# BYH_USBHUB.net
KiCad netlist of a schematic drawn in EasyEDA Pro
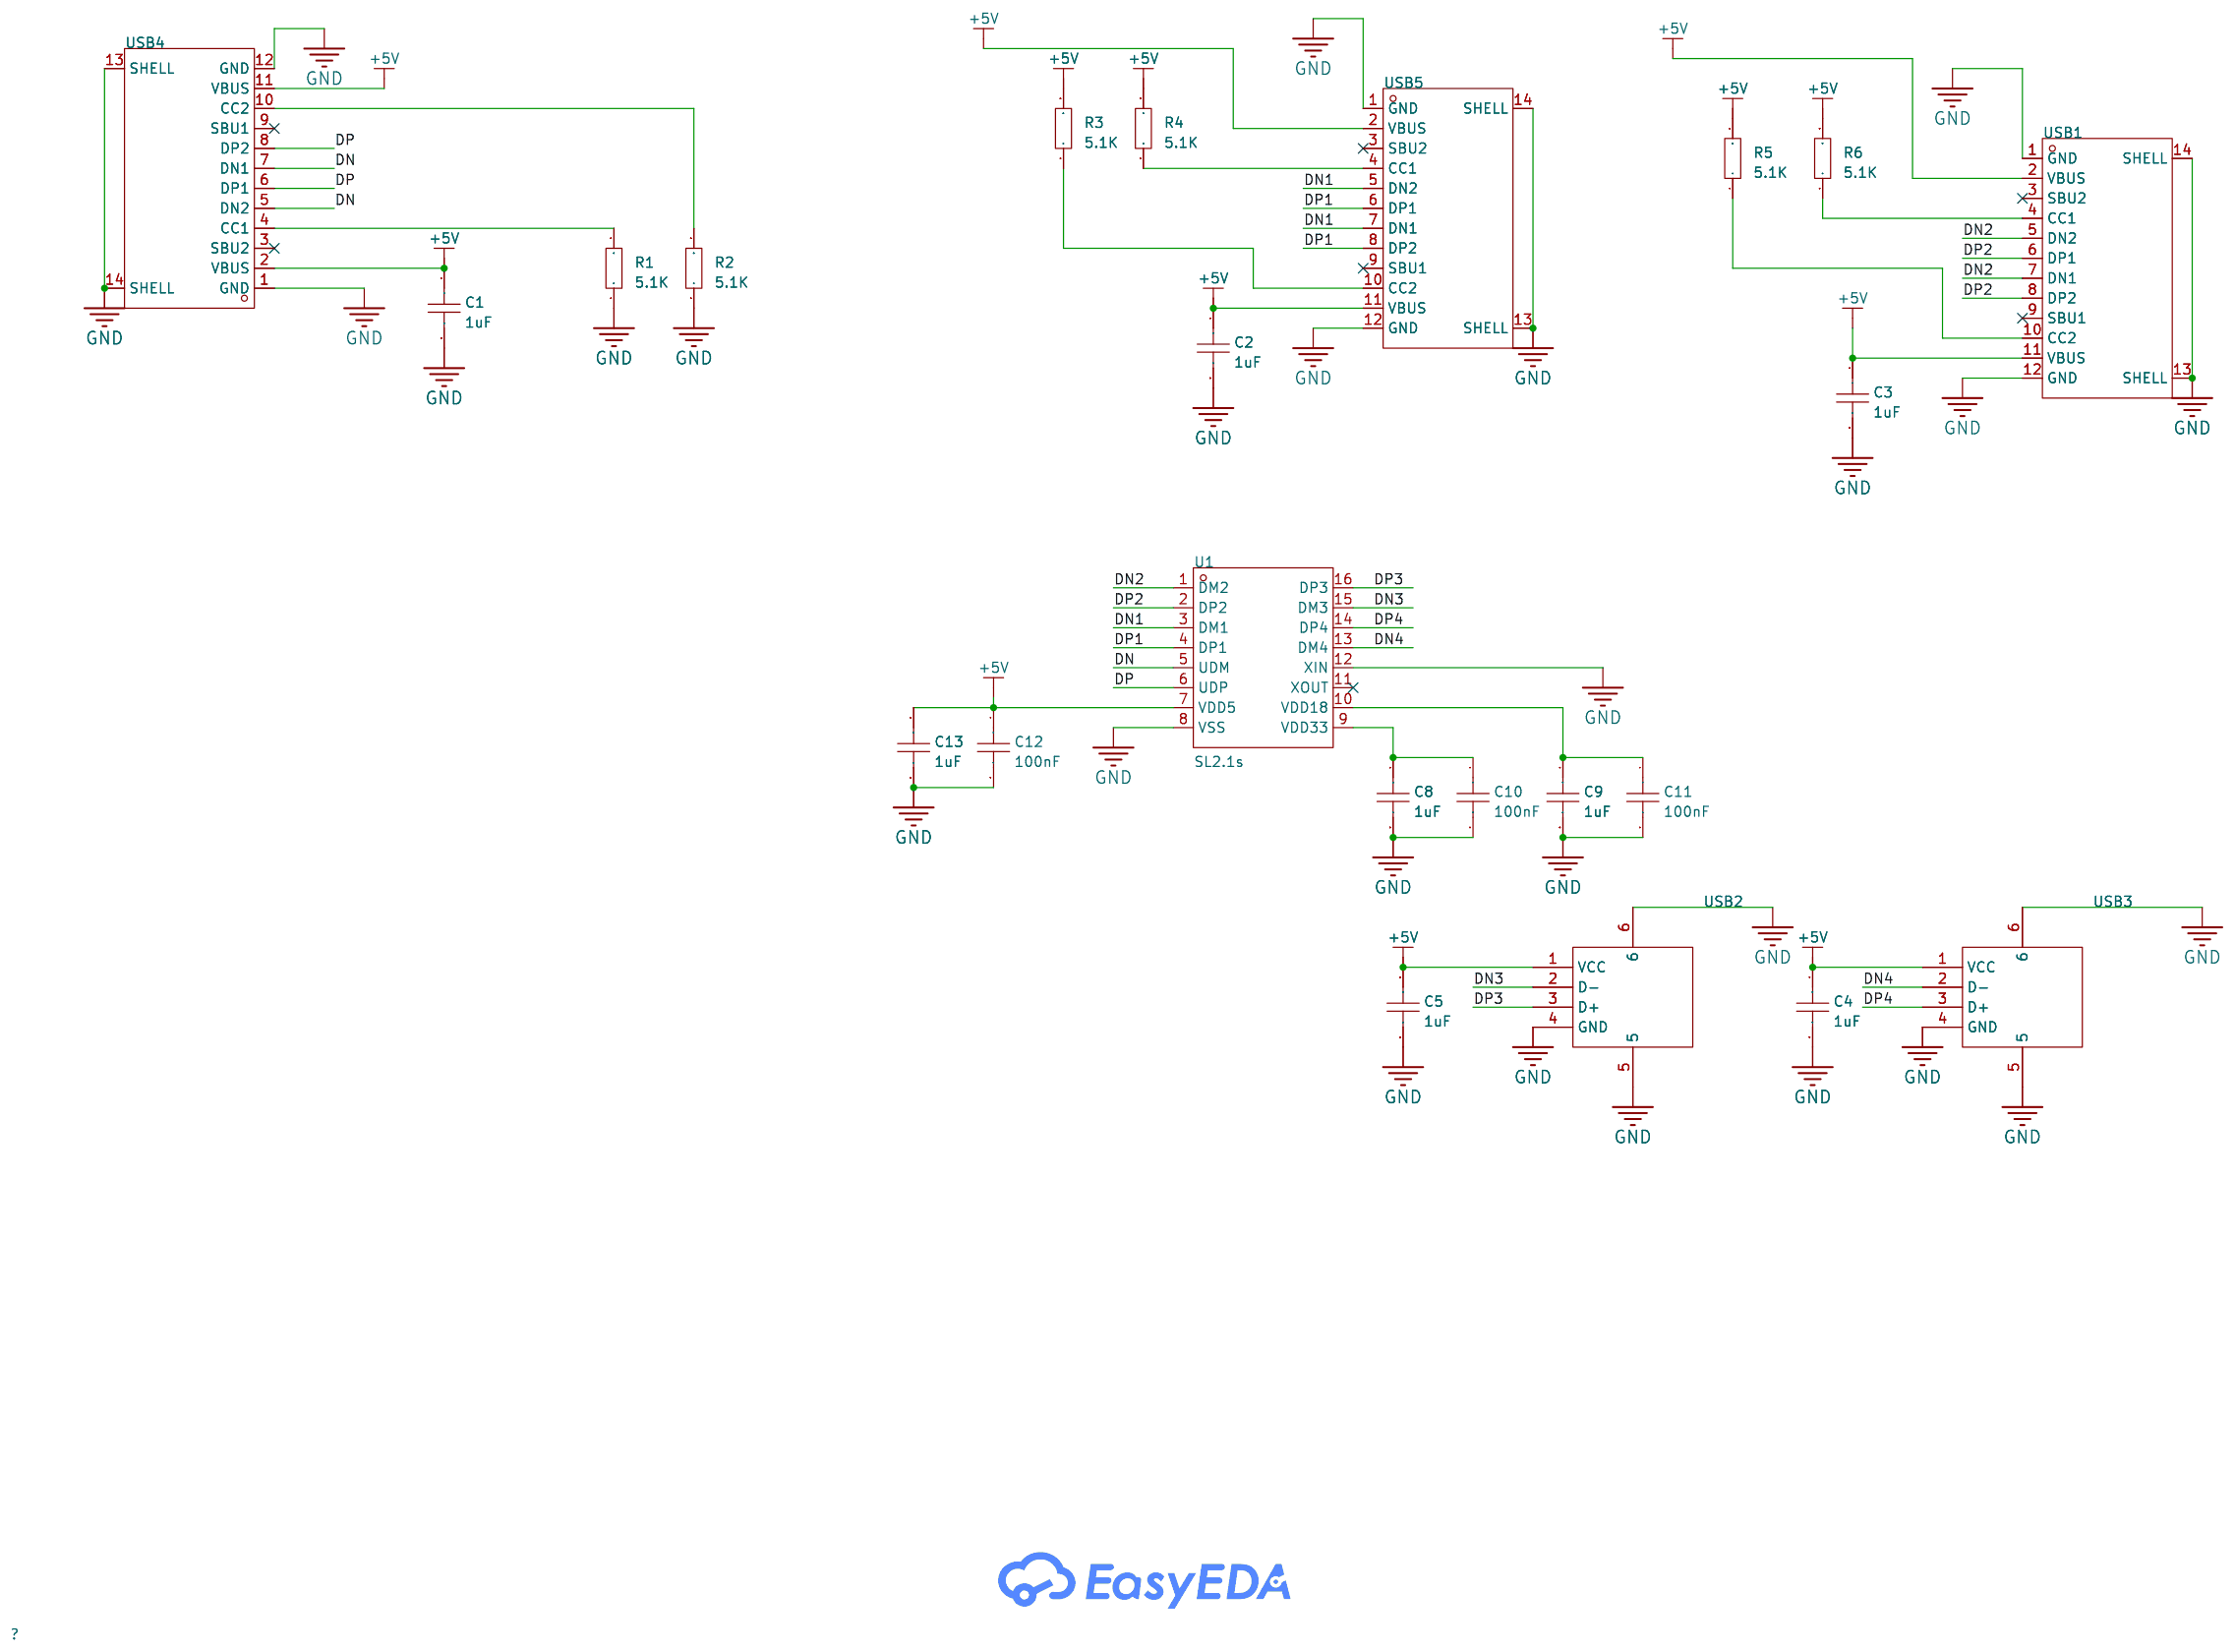
[diagram p0: schematic sheet]

(export (version "E")
  (design (tool "Eeschema 10.0.6"))
  (components
    (comp (ref "C1") (value "1uF") (footprint "easyedapro:C0603") (libsource (lib "easyedapro") (part "CAP")))
    (comp (ref "C2") (value "1uF") (footprint "easyedapro:C0603") (libsource (lib "easyedapro") (part "CAP")))
    (comp (ref "C3") (value "1uF") (footprint "easyedapro:C0603") (libsource (lib "easyedapro") (part "CAP")))
    (comp (ref "C4") (value "1uF") (footprint "easyedapro:C0603") (libsource (lib "easyedapro") (part "CAP")))
    (comp (ref "C5") (value "1uF") (footprint "easyedapro:C0603") (libsource (lib "easyedapro") (part "CAP")))
    (comp (ref "C8") (value "1uF") (footprint "easyedapro:C0603") (libsource (lib "easyedapro") (part "CAP")))
    (comp (ref "C9") (value "1uF") (footprint "easyedapro:C0603") (libsource (lib "easyedapro") (part "CAP")))
    (comp (ref "C10")
      (value "100nF")
      (footprint "easyedapro:C0603")
      (libsource (lib "easyedapro") (part "CAP"))
    )
    (comp (ref "C11")
      (value "100nF")
      (footprint "easyedapro:C0603")
      (libsource (lib "easyedapro") (part "CAP"))
    )
    (comp (ref "C12")
      (value "100nF")
      (footprint "easyedapro:C0603")
      (libsource (lib "easyedapro") (part "CAP"))
    )
    (comp (ref "C13")
      (value "1uF")
      (footprint "easyedapro:C0603")
      (libsource (lib "easyedapro") (part "CAP"))
    )
    (comp (ref "R1")
      (value "5.1K")
      (footprint "easyedapro:R0603")
      (libsource (lib "easyedapro") (part "Res"))
    )
    (comp (ref "R2")
      (value "5.1K")
      (footprint "easyedapro:R0603")
      (libsource (lib "easyedapro") (part "Res"))
    )
    (comp (ref "R3")
      (value "5.1K")
      (footprint "easyedapro:R0603")
      (libsource (lib "easyedapro") (part "Res"))
    )
    (comp (ref "R4")
      (value "5.1K")
      (footprint "easyedapro:R0603")
      (libsource (lib "easyedapro") (part "Res"))
    )
    (comp (ref "R5")
      (value "5.1K")
      (footprint "easyedapro:R0603")
      (libsource (lib "easyedapro") (part "Res"))
    )
    (comp (ref "R6")
      (value "5.1K")
      (footprint "easyedapro:R0603")
      (libsource (lib "easyedapro") (part "Res"))
    )
    (comp (ref "U1")
      (value "SL2.1s")
      (footprint "easyedapro:SSOP-16_L4.6-W2.6-P0.53-LS4.0-BL")
      (fields (field (name "Manufacturer") "CoreChips(和芯润德)"))
      (libsource (lib "easyedapro") (part "SL2.1S"))
    )
    (comp (ref "USB1")
      (value "TYPE-C 16PIN 2MD(073)")
      (footprint "easyedapro:USB-C-SMD_TYPE-C-6PIN-2MD-073")
      (fields (field (name "Manufacturer") "SHOU HAN(首韩)"))
      (libsource (lib "easyedapro") (part "TYPE-C 16PIN 2MD(073)"))
    )
    (comp (ref "USB2")
      (value "10.0 QHHTZB6.3")
      (footprint "easyedapro:USB-A-TH_10.0QHHTZB6.3")
      (fields (field (name "Manufacturer") "SHOU HAN(首韩)"))
      (libsource (lib "easyedapro") (part "10.0 QHHTZB6.3"))
    )
    (comp (ref "USB3")
      (value "10.0 QHHTZB6.3")
      (footprint "easyedapro:USB-A-TH_10.0QHHTZB6.3")
      (fields (field (name "Manufacturer") "SHOU HAN(首韩)"))
      (libsource (lib "easyedapro") (part "10.0 QHHTZB6.3"))
    )
    (comp (ref "USB4")
      (value "TYPE-C 16PIN 2MD(073)")
      (footprint "easyedapro:USB-C-SMD_TYPE-C-6PIN-2MD-073")
      (fields (field (name "Manufacturer") "SHOU HAN(首韩)"))
      (libsource (lib "easyedapro") (part "TYPE-C 16PIN 2MD(073)"))
    )
    (comp (ref "USB5")
      (value "TYPE-C 16PIN 2MD(073)")
      (footprint "easyedapro:USB-C-SMD_TYPE-C-6PIN-2MD-073")
      (fields (field (name "Manufacturer") "SHOU HAN(首韩)"))
      (libsource (lib "easyedapro") (part "TYPE-C 16PIN 2MD(073)"))
    )
  )
  (nets
    (net (code "1") (name "+5V") (class "Default")
      (node (ref "C1") (pin "1") (pinfunction "1_1") (pintype "input"))
      (node (ref "C12") (pin "1") (pinfunction "1_1") (pintype "input"))
      (node (ref "C13") (pin "1") (pinfunction "1_1") (pintype "input"))
      (node (ref "C2") (pin "1") (pinfunction "1_1") (pintype "input"))
      (node (ref "C3") (pin "1") (pinfunction "1_1") (pintype "input"))
      (node (ref "C4") (pin "1") (pinfunction "1_1") (pintype "input"))
      (node (ref "C5") (pin "1") (pinfunction "1_1") (pintype "input"))
      (node (ref "R3") (pin "2") (pinfunction "2_2") (pintype "input"))
      (node (ref "R4") (pin "2") (pinfunction "2_2") (pintype "input"))
      (node (ref "R5") (pin "2") (pinfunction "2_2") (pintype "input"))
      (node (ref "R6") (pin "2") (pinfunction "2_2") (pintype "input"))
      (node (ref "U1") (pin "7") (pinfunction "VDD5_7") (pintype "unspecified"))
      (node (ref "USB1") (pin "11") (pinfunction "VBUS_11") (pintype "unspecified"))
      (node (ref "USB1") (pin "2") (pinfunction "VBUS_2") (pintype "unspecified"))
      (node (ref "USB2") (pin "1") (pinfunction "VCC_1") (pintype "unspecified"))
      (node (ref "USB3") (pin "1") (pinfunction "VCC_1") (pintype "unspecified"))
      (node (ref "USB4") (pin "11") (pinfunction "VBUS_11") (pintype "unspecified"))
      (node (ref "USB4") (pin "2") (pinfunction "VBUS_2") (pintype "unspecified"))
      (node (ref "USB5") (pin "11") (pinfunction "VBUS_11") (pintype "unspecified"))
      (node (ref "USB5") (pin "2") (pinfunction "VBUS_2") (pintype "unspecified"))
    )
    (net (code "2") (name "/DN") (class "Default")
      (node (ref "U1") (pin "5") (pinfunction "UDM_5") (pintype "unspecified"))
      (node (ref "USB4") (pin "5") (pinfunction "DN2_5") (pintype "unspecified"))
      (node (ref "USB4") (pin "7") (pinfunction "DN1_7") (pintype "unspecified"))
    )
    (net (code "3") (name "/DN1") (class "Default")
      (node (ref "U1") (pin "3") (pinfunction "DM1_3") (pintype "unspecified"))
      (node (ref "USB5") (pin "5") (pinfunction "DN2_5") (pintype "unspecified"))
      (node (ref "USB5") (pin "7") (pinfunction "DN1_7") (pintype "unspecified"))
    )
    (net (code "4") (name "/DN2") (class "Default")
      (node (ref "U1") (pin "1") (pinfunction "DM2_1") (pintype "unspecified"))
      (node (ref "USB1") (pin "5") (pinfunction "DN2_5") (pintype "unspecified"))
      (node (ref "USB1") (pin "7") (pinfunction "DN1_7") (pintype "unspecified"))
    )
    (net (code "5") (name "/DN3") (class "Default")
      (node (ref "U1") (pin "15") (pinfunction "DM3_15") (pintype "unspecified"))
      (node (ref "USB2") (pin "2") (pinfunction "D-_2") (pintype "unspecified"))
    )
    (net (code "6") (name "/DN4") (class "Default")
      (node (ref "U1") (pin "13") (pinfunction "DM4_13") (pintype "unspecified"))
      (node (ref "USB3") (pin "2") (pinfunction "D-_2") (pintype "unspecified"))
    )
    (net (code "7") (name "/DP") (class "Default")
      (node (ref "U1") (pin "6") (pinfunction "UDP_6") (pintype "unspecified"))
      (node (ref "USB4") (pin "6") (pinfunction "DP1_6") (pintype "unspecified"))
      (node (ref "USB4") (pin "8") (pinfunction "DP2_8") (pintype "unspecified"))
    )
    (net (code "8") (name "/DP1") (class "Default")
      (node (ref "U1") (pin "4") (pinfunction "DP1_4") (pintype "unspecified"))
      (node (ref "USB5") (pin "6") (pinfunction "DP1_6") (pintype "unspecified"))
      (node (ref "USB5") (pin "8") (pinfunction "DP2_8") (pintype "unspecified"))
    )
    (net (code "9") (name "/DP2") (class "Default")
      (node (ref "U1") (pin "2") (pinfunction "DP2_2") (pintype "unspecified"))
      (node (ref "USB1") (pin "6") (pinfunction "DP1_6") (pintype "unspecified"))
      (node (ref "USB1") (pin "8") (pinfunction "DP2_8") (pintype "unspecified"))
    )
    (net (code "10") (name "/DP3") (class "Default")
      (node (ref "U1") (pin "16") (pinfunction "DP3_16") (pintype "unspecified"))
      (node (ref "USB2") (pin "3") (pinfunction "D+_3") (pintype "unspecified"))
    )
    (net (code "11") (name "/DP4") (class "Default")
      (node (ref "U1") (pin "14") (pinfunction "DP4_14") (pintype "unspecified"))
      (node (ref "USB3") (pin "3") (pinfunction "D+_3") (pintype "unspecified"))
    )
    (net (code "12") (name "GND") (class "Default")
      (node (ref "C1") (pin "2") (pinfunction "2_2") (pintype "input"))
      (node (ref "C10") (pin "2") (pinfunction "2_2") (pintype "input"))
      (node (ref "C11") (pin "2") (pinfunction "2_2") (pintype "input"))
      (node (ref "C12") (pin "2") (pinfunction "2_2") (pintype "input"))
      (node (ref "C13") (pin "2") (pinfunction "2_2") (pintype "input"))
      (node (ref "C2") (pin "2") (pinfunction "2_2") (pintype "input"))
      (node (ref "C3") (pin "2") (pinfunction "2_2") (pintype "input"))
      (node (ref "C4") (pin "2") (pinfunction "2_2") (pintype "input"))
      (node (ref "C5") (pin "2") (pinfunction "2_2") (pintype "input"))
      (node (ref "C8") (pin "2") (pinfunction "2_2") (pintype "input"))
      (node (ref "C9") (pin "2") (pinfunction "2_2") (pintype "input"))
      (node (ref "R1") (pin "1") (pinfunction "1_1") (pintype "input"))
      (node (ref "R2") (pin "1") (pinfunction "1_1") (pintype "input"))
      (node (ref "U1") (pin "12") (pinfunction "XIN_12") (pintype "unspecified"))
      (node (ref "U1") (pin "8") (pinfunction "VSS_8") (pintype "unspecified"))
      (node (ref "USB1") (pin "1") (pinfunction "GND_1") (pintype "unspecified"))
      (node (ref "USB1") (pin "12") (pinfunction "GND_12") (pintype "unspecified"))
      (node (ref "USB1") (pin "13") (pinfunction "SHELL_13") (pintype "unspecified"))
      (node (ref "USB1") (pin "14") (pinfunction "SHELL_14") (pintype "unspecified"))
      (node (ref "USB2") (pin "4") (pinfunction "GND_4") (pintype "unspecified"))
      (node (ref "USB2") (pin "5") (pinfunction "5_5") (pintype "unspecified"))
      (node (ref "USB2") (pin "6") (pinfunction "6_6") (pintype "unspecified"))
      (node (ref "USB3") (pin "4") (pinfunction "GND_4") (pintype "unspecified"))
      (node (ref "USB3") (pin "5") (pinfunction "5_5") (pintype "unspecified"))
      (node (ref "USB3") (pin "6") (pinfunction "6_6") (pintype "unspecified"))
      (node (ref "USB4") (pin "1") (pinfunction "GND_1") (pintype "unspecified"))
      (node (ref "USB4") (pin "12") (pinfunction "GND_12") (pintype "unspecified"))
      (node (ref "USB4") (pin "13") (pinfunction "SHELL_13") (pintype "unspecified"))
      (node (ref "USB4") (pin "14") (pinfunction "SHELL_14") (pintype "unspecified"))
      (node (ref "USB5") (pin "1") (pinfunction "GND_1") (pintype "unspecified"))
      (node (ref "USB5") (pin "12") (pinfunction "GND_12") (pintype "unspecified"))
      (node (ref "USB5") (pin "13") (pinfunction "SHELL_13") (pintype "unspecified"))
      (node (ref "USB5") (pin "14") (pinfunction "SHELL_14") (pintype "unspecified"))
    )
    (net (code "13") (name "Net-(U1-VDD18)") (class "Default")
      (node (ref "C11") (pin "1") (pinfunction "1_1") (pintype "input"))
      (node (ref "C9") (pin "1") (pinfunction "1_1") (pintype "input"))
      (node (ref "U1") (pin "10") (pinfunction "VDD18_10") (pintype "unspecified"))
    )
    (net (code "14") (name "Net-(U1-VDD33)") (class "Default")
      (node (ref "C10") (pin "1") (pinfunction "1_1") (pintype "input"))
      (node (ref "C8") (pin "1") (pinfunction "1_1") (pintype "input"))
      (node (ref "U1") (pin "9") (pinfunction "VDD33_9") (pintype "unspecified"))
    )
    (net (code "15") (name "Net-(USB1-CC1)") (class "Default")
      (node (ref "R6") (pin "1") (pinfunction "1_1") (pintype "input"))
      (node (ref "USB1") (pin "4") (pinfunction "CC1_4") (pintype "unspecified"))
    )
    (net (code "16") (name "Net-(USB1-CC2)") (class "Default")
      (node (ref "R5") (pin "1") (pinfunction "1_1") (pintype "input"))
      (node (ref "USB1") (pin "10") (pinfunction "CC2_10") (pintype "unspecified"))
    )
    (net (code "17") (name "Net-(USB4-CC1)") (class "Default")
      (node (ref "R1") (pin "2") (pinfunction "2_2") (pintype "input"))
      (node (ref "USB4") (pin "4") (pinfunction "CC1_4") (pintype "unspecified"))
    )
    (net (code "18") (name "Net-(USB4-CC2)") (class "Default")
      (node (ref "R2") (pin "2") (pinfunction "2_2") (pintype "input"))
      (node (ref "USB4") (pin "10") (pinfunction "CC2_10") (pintype "unspecified"))
    )
    (net (code "19") (name "Net-(USB5-CC1)") (class "Default")
      (node (ref "R4") (pin "1") (pinfunction "1_1") (pintype "input"))
      (node (ref "USB5") (pin "4") (pinfunction "CC1_4") (pintype "unspecified"))
    )
    (net (code "20") (name "Net-(USB5-CC2)") (class "Default")
      (node (ref "R3") (pin "1") (pinfunction "1_1") (pintype "input"))
      (node (ref "USB5") (pin "10") (pinfunction "CC2_10") (pintype "unspecified"))
    )
    (net (code "21") (name "unconnected-(U1-XOUT-Pad11)") (class "Default")
      (node (ref "U1") (pin "11") (pinfunction "XOUT_11") (pintype "unspecified+no_connect"))
    )
    (net (code "22") (name "unconnected-(USB1-SBU1-Pad9)") (class "Default")
      (node (ref "USB1") (pin "9") (pinfunction "SBU1_9") (pintype "unspecified+no_connect"))
    )
    (net (code "23") (name "unconnected-(USB1-SBU2-Pad3)") (class "Default")
      (node (ref "USB1") (pin "3") (pinfunction "SBU2_3") (pintype "unspecified+no_connect"))
    )
    (net (code "24") (name "unconnected-(USB4-SBU1-Pad9)") (class "Default")
      (node (ref "USB4") (pin "9") (pinfunction "SBU1_9") (pintype "unspecified+no_connect"))
    )
    (net (code "25") (name "unconnected-(USB4-SBU2-Pad3)") (class "Default")
      (node (ref "USB4") (pin "3") (pinfunction "SBU2_3") (pintype "unspecified+no_connect"))
    )
    (net (code "26") (name "unconnected-(USB5-SBU1-Pad9)") (class "Default")
      (node (ref "USB5") (pin "9") (pinfunction "SBU1_9") (pintype "unspecified+no_connect"))
    )
    (net (code "27") (name "unconnected-(USB5-SBU2-Pad3)") (class "Default")
      (node (ref "USB5") (pin "3") (pinfunction "SBU2_3") (pintype "unspecified+no_connect"))
    )
  )
)
